# Power_Supply.net
KiCad netlist of a schematic drawn in Altium Designer
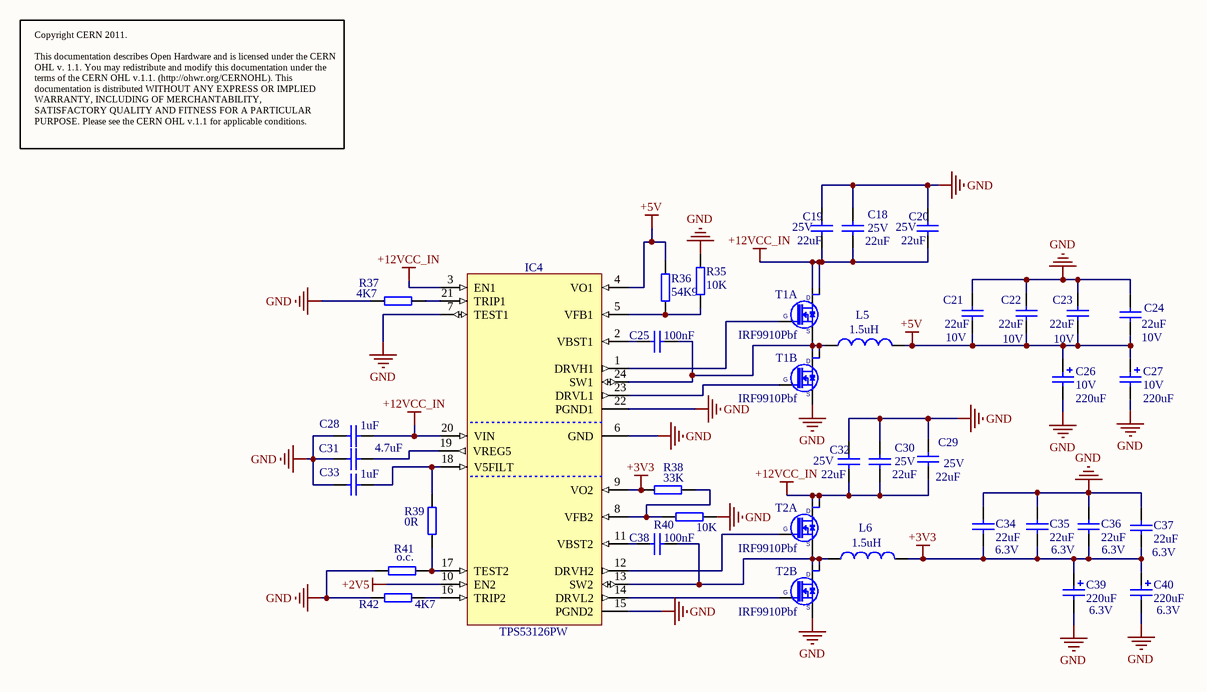
[diagram p0: Power_Supply.SchDoc]

(export (version "E")
  (design (tool "Eeschema 10.0.6"))
  (components
    (comp (ref "C18")
      (value "22uF")
      (footprint "CC3216-1206")
      (description "Capacitor")
      (fields
        (field (name "TOLERANCE") "±10%")
        (field (name "VOLTAGE") "25V")
        (field (name "Comment") "22uF 25V")
        (field (name "PUBLISHER") "Altium Limited")
      )
      (libsource (lib "wr_switch") (part "Cap"))
    )
    (comp (ref "C19")
      (value "22uF")
      (footprint "CC3216-1206")
      (description "Capacitor")
      (fields
        (field (name "TOLERANCE") "±10%")
        (field (name "VOLTAGE") "25V")
        (field (name "Comment") "22uF 25V")
        (field (name "PUBLISHER") "Altium Limited")
      )
      (libsource (lib "wr_switch") (part "Cap"))
    )
    (comp (ref "C20")
      (value "22uF")
      (footprint "CC3216-1206")
      (description "Capacitor")
      (fields
        (field (name "TOLERANCE") "±10%")
        (field (name "VOLTAGE") "25V")
        (field (name "Comment") "22uF 25V")
        (field (name "PUBLISHER") "Altium Limited")
      )
      (libsource (lib "wr_switch") (part "Cap"))
    )
    (comp (ref "C21")
      (value "22uF")
      (footprint "CC2012-0805")
      (description "Capacitor")
      (fields
        (field (name "TOLERANCE") "±10%")
        (field (name "VOLTAGE") "10V")
        (field (name "Comment") "22uF 10V")
        (field (name "PUBLISHER") "Altium Limited")
      )
      (libsource (lib "wr_switch") (part "Cap"))
    )
    (comp (ref "C22")
      (value "22uF")
      (footprint "CC2012-0805")
      (description "Capacitor")
      (fields
        (field (name "TOLERANCE") "±10%")
        (field (name "VOLTAGE") "10V")
        (field (name "Comment") "22uF 10V")
        (field (name "PUBLISHER") "Altium Limited")
      )
      (libsource (lib "wr_switch") (part "Cap"))
    )
    (comp (ref "C23")
      (value "22uF")
      (footprint "CC2012-0805")
      (description "Capacitor")
      (fields
        (field (name "TOLERANCE") "±10%")
        (field (name "VOLTAGE") "10V")
        (field (name "Comment") "22uF 10V")
        (field (name "PUBLISHER") "Altium Limited")
      )
      (libsource (lib "wr_switch") (part "Cap"))
    )
    (comp (ref "C24")
      (value "22uF")
      (footprint "CC2012-0805")
      (description "Capacitor")
      (fields
        (field (name "TOLERANCE") "±10%")
        (field (name "VOLTAGE") "10V")
        (field (name "Comment") "22uF 10V")
        (field (name "PUBLISHER") "Altium Limited")
      )
      (libsource (lib "wr_switch") (part "Cap"))
    )
    (comp (ref "C25")
      (value "100nF")
      (footprint "CC1608-0603")
      (description "Capacitor")
      (fields
        (field (name "TOLERANCE") "±10%")
        (field (name "VOLTAGE") "16V")
        (field (name "PUBLISHER") "Altium Limited")
      )
      (libsource (lib "wr_switch") (part "Cap"))
    )
    (comp (ref "C26")
      (value "220uF")
      (footprint "D")
      (description "Polarized Capacitor Tantalum")
      (fields
        (field (name "TOLERANCE") "±20%")
        (field (name "VOLTAGE") "10V")
        (field (name "Comment") "220uF 10V")
        (field (name "PUBLISHER") "Altium Limited")
      )
      (libsource (lib "wr_switch") (part "Cap Pol1"))
    )
    (comp (ref "C27")
      (value "220uF")
      (footprint "D")
      (description "Polarized Capacitor Tantalum")
      (fields
        (field (name "TOLERANCE") "±20%")
        (field (name "VOLTAGE") "10V")
        (field (name "Comment") "220uF 10V")
        (field (name "PUBLISHER") "Altium Limited")
      )
      (libsource (lib "wr_switch") (part "Cap Pol1"))
    )
    (comp (ref "C28")
      (value "1uF")
      (footprint "CC1608-0603")
      (description "Capacitor")
      (fields
        (field (name "TOLERANCE") "±10%")
        (field (name "VOLTAGE") "25V")
        (field (name "PUBLISHER") "Altium Limited")
      )
      (libsource (lib "wr_switch") (part "Cap"))
    )
    (comp (ref "C29")
      (value "22uF")
      (footprint "CC3216-1206")
      (description "Capacitor")
      (fields
        (field (name "TOLERANCE") "±10%")
        (field (name "VOLTAGE") "25V")
        (field (name "Comment") "22uF 25V")
        (field (name "PUBLISHER") "Altium Limited")
      )
      (libsource (lib "wr_switch") (part "Cap"))
    )
    (comp (ref "C30")
      (value "22uF")
      (footprint "CC3216-1206")
      (description "Capacitor")
      (fields
        (field (name "TOLERANCE") "±10%")
        (field (name "VOLTAGE") "25V")
        (field (name "Comment") "22uF 25V")
        (field (name "PUBLISHER") "Altium Limited")
      )
      (libsource (lib "wr_switch") (part "Cap"))
    )
    (comp (ref "C31")
      (value "4.7uF")
      (footprint "CC1608-0603")
      (description "Capacitor")
      (fields
        (field (name "TOLERANCE") "±10%")
        (field (name "VOLTAGE") "10V")
        (field (name "PUBLISHER") "Altium Limited")
      )
      (libsource (lib "wr_switch") (part "Cap"))
    )
    (comp (ref "C32")
      (value "22uF")
      (footprint "CC3216-1206")
      (description "Capacitor")
      (fields
        (field (name "TOLERANCE") "±10%")
        (field (name "VOLTAGE") "25V")
        (field (name "Comment") "22uF 25V")
        (field (name "PUBLISHER") "Altium Limited")
      )
      (libsource (lib "wr_switch") (part "Cap"))
    )
    (comp (ref "C33")
      (value "1uF")
      (footprint "CC1608-0603")
      (description "Capacitor")
      (fields
        (field (name "TOLERANCE") "±10%")
        (field (name "VOLTAGE") "25V")
        (field (name "PUBLISHER") "Altium Limited")
      )
      (libsource (lib "wr_switch") (part "Cap"))
    )
    (comp (ref "C34")
      (value "22uF")
      (footprint "CC2012-0805")
      (description "Capacitor")
      (fields
        (field (name "TOLERANCE") "±20%")
        (field (name "VOLTAGE") "6.3V")
        (field (name "PUBLISHER") "Altium Limited")
      )
      (libsource (lib "wr_switch") (part "Cap"))
    )
    (comp (ref "C35")
      (value "22uF")
      (footprint "CC2012-0805")
      (description "Capacitor")
      (fields
        (field (name "TOLERANCE") "±20%")
        (field (name "VOLTAGE") "6.3V")
        (field (name "PUBLISHER") "Altium Limited")
      )
      (libsource (lib "wr_switch") (part "Cap"))
    )
    (comp (ref "C36")
      (value "22uF")
      (footprint "CC2012-0805")
      (description "Capacitor")
      (fields
        (field (name "TOLERANCE") "±20%")
        (field (name "VOLTAGE") "6.3V")
        (field (name "PUBLISHER") "Altium Limited")
      )
      (libsource (lib "wr_switch") (part "Cap"))
    )
    (comp (ref "C37")
      (value "22uF")
      (footprint "CC2012-0805")
      (description "Capacitor")
      (fields
        (field (name "TOLERANCE") "±20%")
        (field (name "VOLTAGE") "6.3V")
        (field (name "PUBLISHER") "Altium Limited")
      )
      (libsource (lib "wr_switch") (part "Cap"))
    )
    (comp (ref "C38")
      (value "100nF")
      (footprint "CC1608-0603")
      (description "Capacitor")
      (fields
        (field (name "TOLERANCE") "±10%")
        (field (name "VOLTAGE") "16V")
        (field (name "PUBLISHER") "Altium Limited")
      )
      (libsource (lib "wr_switch") (part "Cap"))
    )
    (comp (ref "C39")
      (value "220uF")
      (footprint "D")
      (description "Polarized Capacitor Tantalum")
      (fields
        (field (name "TOLERANCE") "±20%")
        (field (name "VOLTAGE") "6.3V")
        (field (name "PUBLISHER") "Altium Limited")
      )
      (libsource (lib "wr_switch") (part "Cap Pol1"))
    )
    (comp (ref "C40")
      (value "220uF")
      (footprint "D")
      (description "Polarized Capacitor Tantalum")
      (fields
        (field (name "TOLERANCE") "±20%")
        (field (name "VOLTAGE") "6.3V")
        (field (name "PUBLISHER") "Altium Limited")
      )
      (libsource (lib "wr_switch") (part "Cap Pol1"))
    )
    (comp (ref "IC4")
      (value "TPS53126PW")
      (footprint "SOP65P640X120-24N")
      (description "Dual Synchronous Step-Down Controller For Low Voltage Power Rails")
      (fields (field (name "AUTHOR") "CERN DEM JLC"))
      (libsource (lib "wr_switch") (part "TPS53126PW"))
    )
    (comp (ref "L5")
      (value "1.5uH")
      (footprint "IHLP2525")
      (description "Low Profile, High Current Inductor")
      (fields
        (field (name "MANUFACTURER") "Vishay/Dale")
        (field (name "Comment") "IHLP2525CZER1R5M01")
        (field (name "PUBLISHER") "Altium Limited")
      )
      (libsource (lib "Miscellaneous Devices") (part "Inductor"))
    )
    (comp (ref "L6")
      (value "1.5uH")
      (footprint "IHLP2525")
      (description "Low Profile, High Current Inductor")
      (fields
        (field (name "MANUFACTURER") "Vishay/Dale")
        (field (name "Comment") "IHLP2525CZER1R5M01")
        (field (name "PUBLISHER") "Altium Limited")
      )
      (libsource (lib "Miscellaneous Devices") (part "Inductor"))
    )
    (comp (ref "R35")
      (value "10K")
      (footprint "0603")
      (description "SMD Resistor")
      (fields (field (name "TOLERANCE") "±1%"))
      (libsource (lib "wr_switch") (part "RES_SMD"))
    )
    (comp (ref "R36")
      (value "54K9")
      (footprint "0603")
      (description "SMD Resistor")
      (fields (field (name "TOLERANCE") "±1%"))
      (libsource (lib "wr_switch") (part "RES_SMD"))
    )
    (comp (ref "R37")
      (value "4K7")
      (footprint "0603")
      (description "SMD Resistor")
      (fields (field (name "TOLERANCE") "±1%"))
      (libsource (lib "wr_switch") (part "RES_SMD"))
    )
    (comp (ref "R38")
      (value "33K")
      (footprint "0603")
      (description "SMD Resistor")
      (fields (field (name "TOLERANCE") "±1%"))
      (libsource (lib "wr_switch") (part "RES_SMD"))
    )
    (comp (ref "R39")
      (value "0R")
      (footprint "0603")
      (description "SMD Resistor")
      (libsource (lib "wr_switch") (part "RES_SMD"))
    )
    (comp (ref "R40")
      (value "10K")
      (footprint "0603")
      (description "SMD Resistor")
      (fields (field (name "TOLERANCE") "±1%"))
      (libsource (lib "wr_switch") (part "RES_SMD"))
    )
    (comp (ref "R41")
      (value "o.c.")
      (footprint "0603")
      (description "SMD Resistor")
      (fields (field (name "TOLERANCE") "NA"))
      (libsource (lib "wr_switch") (part "RES_SMD"))
    )
    (comp (ref "R42")
      (value "4K7")
      (footprint "0603")
      (description "SMD Resistor")
      (fields (field (name "TOLERANCE") "±1%"))
      (libsource (lib "wr_switch") (part "RES_SMD"))
    )
    (comp (ref "T1")
      (value "IRF9910Pbf")
      (footprint "SOIC127P600X175-8N")
      (description "Dual SO-8 MOSFET For POL Cconverter")
      (fields (field (name "MANUFACTURER") "INTERNATIONAL RECTIFIER") (field (name "AUTHOR") "CERN DEM JLC"))
      (libsource (lib "ICs And Semiconductors") (part "IRF9910"))
    )
    (comp (ref "T2")
      (value "IRF9910Pbf")
      (footprint "SOIC127P600X175-8N")
      (description "Dual SO-8 MOSFET For POL Cconverter")
      (fields (field (name "MANUFACTURER") "INTERNATIONAL RECTIFIER") (field (name "AUTHOR") "CERN DEM JLC"))
      (libsource (lib "ICs And Semiconductors") (part "IRF9910"))
    )
  )
  (nets
    (net (code "1") (name "+2V5") (class "Default")
      (node (ref "IC4") (pin "10") (pinfunction "EN2_10") (pintype "input"))
    )
    (net (code "2") (name "+3V3") (class "Default")
      (node (ref "C34") (pin "2") (pinfunction "2_2") (pintype "passive"))
      (node (ref "C35") (pin "1") (pinfunction "1_1") (pintype "passive"))
      (node (ref "C36") (pin "1") (pinfunction "1_1") (pintype "passive"))
      (node (ref "C37") (pin "1") (pinfunction "1_1") (pintype "passive"))
      (node (ref "C39") (pin "1") (pinfunction "1_1") (pintype "passive"))
      (node (ref "C40") (pin "1") (pinfunction "1_1") (pintype "passive"))
      (node (ref "IC4") (pin "9") (pinfunction "VO2_9") (pintype "input"))
      (node (ref "L6") (pin "2") (pinfunction "2_2") (pintype "passive"))
      (node (ref "R38") (pin "1") (pinfunction "1_1") (pintype "passive"))
    )
    (net (code "3") (name "+5V") (class "Default")
      (node (ref "C21") (pin "1") (pinfunction "1_1") (pintype "passive"))
      (node (ref "C22") (pin "1") (pinfunction "1_1") (pintype "passive"))
      (node (ref "C23") (pin "1") (pinfunction "1_1") (pintype "passive"))
      (node (ref "C24") (pin "1") (pinfunction "1_1") (pintype "passive"))
      (node (ref "C26") (pin "1") (pinfunction "1_1") (pintype "passive"))
      (node (ref "C27") (pin "1") (pinfunction "1_1") (pintype "passive"))
      (node (ref "IC4") (pin "4") (pinfunction "VO1_4") (pintype "input"))
      (node (ref "L5") (pin "2") (pinfunction "2_2") (pintype "passive"))
      (node (ref "R36") (pin "2") (pinfunction "2_2") (pintype "passive"))
    )
    (net (code "4") (name "+12VCC_IN") (class "Default")
      (node (ref "C18") (pin "1") (pinfunction "1_1") (pintype "passive"))
      (node (ref "C19") (pin "1") (pinfunction "1_1") (pintype "passive"))
      (node (ref "C20") (pin "1") (pinfunction "1_1") (pintype "passive"))
      (node (ref "C28") (pin "2") (pinfunction "2_2") (pintype "passive"))
      (node (ref "C29") (pin "1") (pinfunction "1_1") (pintype "passive"))
      (node (ref "C30") (pin "1") (pinfunction "1_1") (pintype "passive"))
      (node (ref "C32") (pin "1") (pinfunction "1_1") (pintype "passive"))
      (node (ref "IC4") (pin "20") (pinfunction "VIN_20") (pintype "input"))
      (node (ref "IC4") (pin "3") (pinfunction "EN1_3") (pintype "input"))
      (node (ref "T1") (pin "5") (pinfunction "D_5") (pintype "passive"))
      (node (ref "T1") (pin "6") (pinfunction "D_6") (pintype "passive"))
      (node (ref "T2") (pin "5") (pinfunction "D_5") (pintype "passive"))
      (node (ref "T2") (pin "6") (pinfunction "D_6") (pintype "passive"))
    )
    (net (code "5") (name "GND") (class "Default")
      (node (ref "C18") (pin "2") (pinfunction "2_2") (pintype "passive"))
      (node (ref "C19") (pin "2") (pinfunction "2_2") (pintype "passive"))
      (node (ref "C20") (pin "2") (pinfunction "2_2") (pintype "passive"))
      (node (ref "C21") (pin "2") (pinfunction "2_2") (pintype "passive"))
      (node (ref "C22") (pin "2") (pinfunction "2_2") (pintype "passive"))
      (node (ref "C23") (pin "2") (pinfunction "2_2") (pintype "passive"))
      (node (ref "C24") (pin "2") (pinfunction "2_2") (pintype "passive"))
      (node (ref "C26") (pin "2") (pinfunction "2_2") (pintype "passive"))
      (node (ref "C27") (pin "2") (pinfunction "2_2") (pintype "passive"))
      (node (ref "C28") (pin "1") (pinfunction "1_1") (pintype "passive"))
      (node (ref "C29") (pin "2") (pinfunction "2_2") (pintype "passive"))
      (node (ref "C30") (pin "2") (pinfunction "2_2") (pintype "passive"))
      (node (ref "C31") (pin "2") (pinfunction "2_2") (pintype "passive"))
      (node (ref "C32") (pin "2") (pinfunction "2_2") (pintype "passive"))
      (node (ref "C33") (pin "1") (pinfunction "1_1") (pintype "passive"))
      (node (ref "C34") (pin "1") (pinfunction "1_1") (pintype "passive"))
      (node (ref "C35") (pin "2") (pinfunction "2_2") (pintype "passive"))
      (node (ref "C36") (pin "2") (pinfunction "2_2") (pintype "passive"))
      (node (ref "C37") (pin "2") (pinfunction "2_2") (pintype "passive"))
      (node (ref "C39") (pin "2") (pinfunction "2_2") (pintype "passive"))
      (node (ref "C40") (pin "2") (pinfunction "2_2") (pintype "passive"))
      (node (ref "IC4") (pin "15") (pinfunction "PGND2_15") (pintype "power_in"))
      (node (ref "IC4") (pin "22") (pinfunction "PGND1_22") (pintype "power_in"))
      (node (ref "IC4") (pin "6") (pinfunction "GND_6") (pintype "power_in"))
      (node (ref "IC4") (pin "7") (pinfunction "TEST1_7") (pintype "bidirectional"))
      (node (ref "R35") (pin "2") (pinfunction "2_2") (pintype "passive"))
      (node (ref "R37") (pin "2") (pinfunction "2_2") (pintype "passive"))
      (node (ref "R40") (pin "1") (pinfunction "1_1") (pintype "passive"))
      (node (ref "R41") (pin "2") (pinfunction "2_2") (pintype "passive"))
      (node (ref "R42") (pin "2") (pinfunction "2_2") (pintype "passive"))
      (node (ref "T1") (pin "1") (pinfunction "S_1") (pintype "passive"))
      (node (ref "T2") (pin "1") (pinfunction "S_1") (pintype "passive"))
    )
    (net (code "6") (name "Net-(IC4-DRVH1)") (class "Default")
      (node (ref "IC4") (pin "1") (pinfunction "DRVH1_1") (pintype "output"))
      (node (ref "T1") (pin "4") (pinfunction "G_4") (pintype "passive"))
    )
    (net (code "7") (name "Net-(IC4-DRVH2)") (class "Default")
      (node (ref "IC4") (pin "12") (pinfunction "DRVH2_12") (pintype "output"))
      (node (ref "T2") (pin "4") (pinfunction "G_4") (pintype "passive"))
    )
    (net (code "8") (name "Net-(IC4-DRVL1)") (class "Default")
      (node (ref "IC4") (pin "23") (pinfunction "DRVL1_23") (pintype "output"))
      (node (ref "T1") (pin "2") (pinfunction "G_2") (pintype "passive"))
    )
    (net (code "9") (name "Net-(IC4-DRVL2)") (class "Default")
      (node (ref "IC4") (pin "14") (pinfunction "DRVL2_14") (pintype "output"))
      (node (ref "T2") (pin "2") (pinfunction "G_2") (pintype "passive"))
    )
    (net (code "10") (name "Net-(IC4-SW1)") (class "Default")
      (node (ref "C25") (pin "1") (pinfunction "1_1") (pintype "passive"))
      (node (ref "IC4") (pin "24") (pinfunction "SW1_24") (pintype "bidirectional"))
      (node (ref "L5") (pin "1") (pinfunction "1_1") (pintype "passive"))
      (node (ref "T1") (pin "3") (pinfunction "S_3") (pintype "passive"))
      (node (ref "T1") (pin "7") (pinfunction "D_7") (pintype "passive"))
      (node (ref "T1") (pin "8") (pinfunction "D_8") (pintype "passive"))
    )
    (net (code "11") (name "Net-(IC4-SW2)") (class "Default")
      (node (ref "C38") (pin "1") (pinfunction "1_1") (pintype "passive"))
      (node (ref "IC4") (pin "13") (pinfunction "SW2_13") (pintype "bidirectional"))
      (node (ref "L6") (pin "1") (pinfunction "1_1") (pintype "passive"))
      (node (ref "T2") (pin "3") (pinfunction "S_3") (pintype "passive"))
      (node (ref "T2") (pin "7") (pinfunction "D_7") (pintype "passive"))
      (node (ref "T2") (pin "8") (pinfunction "D_8") (pintype "passive"))
    )
    (net (code "12") (name "Net-(IC4-TEST2)") (class "Default")
      (node (ref "IC4") (pin "17") (pinfunction "TEST2_17") (pintype "input"))
      (node (ref "R39") (pin "2") (pinfunction "2_2") (pintype "passive"))
      (node (ref "R41") (pin "1") (pinfunction "1_1") (pintype "passive"))
    )
    (net (code "13") (name "Net-(IC4-TRIP1)") (class "Default")
      (node (ref "IC4") (pin "21") (pinfunction "TRIP1_21") (pintype "input"))
      (node (ref "R37") (pin "1") (pinfunction "1_1") (pintype "passive"))
    )
    (net (code "14") (name "Net-(IC4-TRIP2)") (class "Default")
      (node (ref "IC4") (pin "16") (pinfunction "TRIP2_16") (pintype "input"))
      (node (ref "R42") (pin "1") (pinfunction "1_1") (pintype "passive"))
    )
    (net (code "15") (name "Net-(IC4-V5FILT)") (class "Default")
      (node (ref "C33") (pin "2") (pinfunction "2_2") (pintype "passive"))
      (node (ref "IC4") (pin "18") (pinfunction "V5FILT_18") (pintype "input"))
      (node (ref "R39") (pin "1") (pinfunction "1_1") (pintype "passive"))
    )
    (net (code "16") (name "Net-(IC4-VBST1)") (class "Default")
      (node (ref "C25") (pin "2") (pinfunction "2_2") (pintype "passive"))
      (node (ref "IC4") (pin "2") (pinfunction "VBST1_2") (pintype "input"))
    )
    (net (code "17") (name "Net-(IC4-VBST2)") (class "Default")
      (node (ref "C38") (pin "2") (pinfunction "2_2") (pintype "passive"))
      (node (ref "IC4") (pin "11") (pinfunction "VBST2_11") (pintype "input"))
    )
    (net (code "18") (name "Net-(IC4-VFB1)") (class "Default")
      (node (ref "IC4") (pin "5") (pinfunction "VFB1_5") (pintype "input"))
      (node (ref "R35") (pin "1") (pinfunction "1_1") (pintype "passive"))
      (node (ref "R36") (pin "1") (pinfunction "1_1") (pintype "passive"))
    )
    (net (code "19") (name "Net-(IC4-VFB2)") (class "Default")
      (node (ref "IC4") (pin "8") (pinfunction "VFB2_8") (pintype "input"))
      (node (ref "R38") (pin "2") (pinfunction "2_2") (pintype "passive"))
      (node (ref "R40") (pin "2") (pinfunction "2_2") (pintype "passive"))
    )
    (net (code "20") (name "Net-(IC4-VREG5)") (class "Default")
      (node (ref "C31") (pin "1") (pinfunction "1_1") (pintype "passive"))
      (node (ref "IC4") (pin "19") (pinfunction "VREG5_19") (pintype "output"))
    )
  )
)
